# SCH_ea-masterboard_2025-10-05.net
KiCad netlist of a schematic drawn in EasyEDA
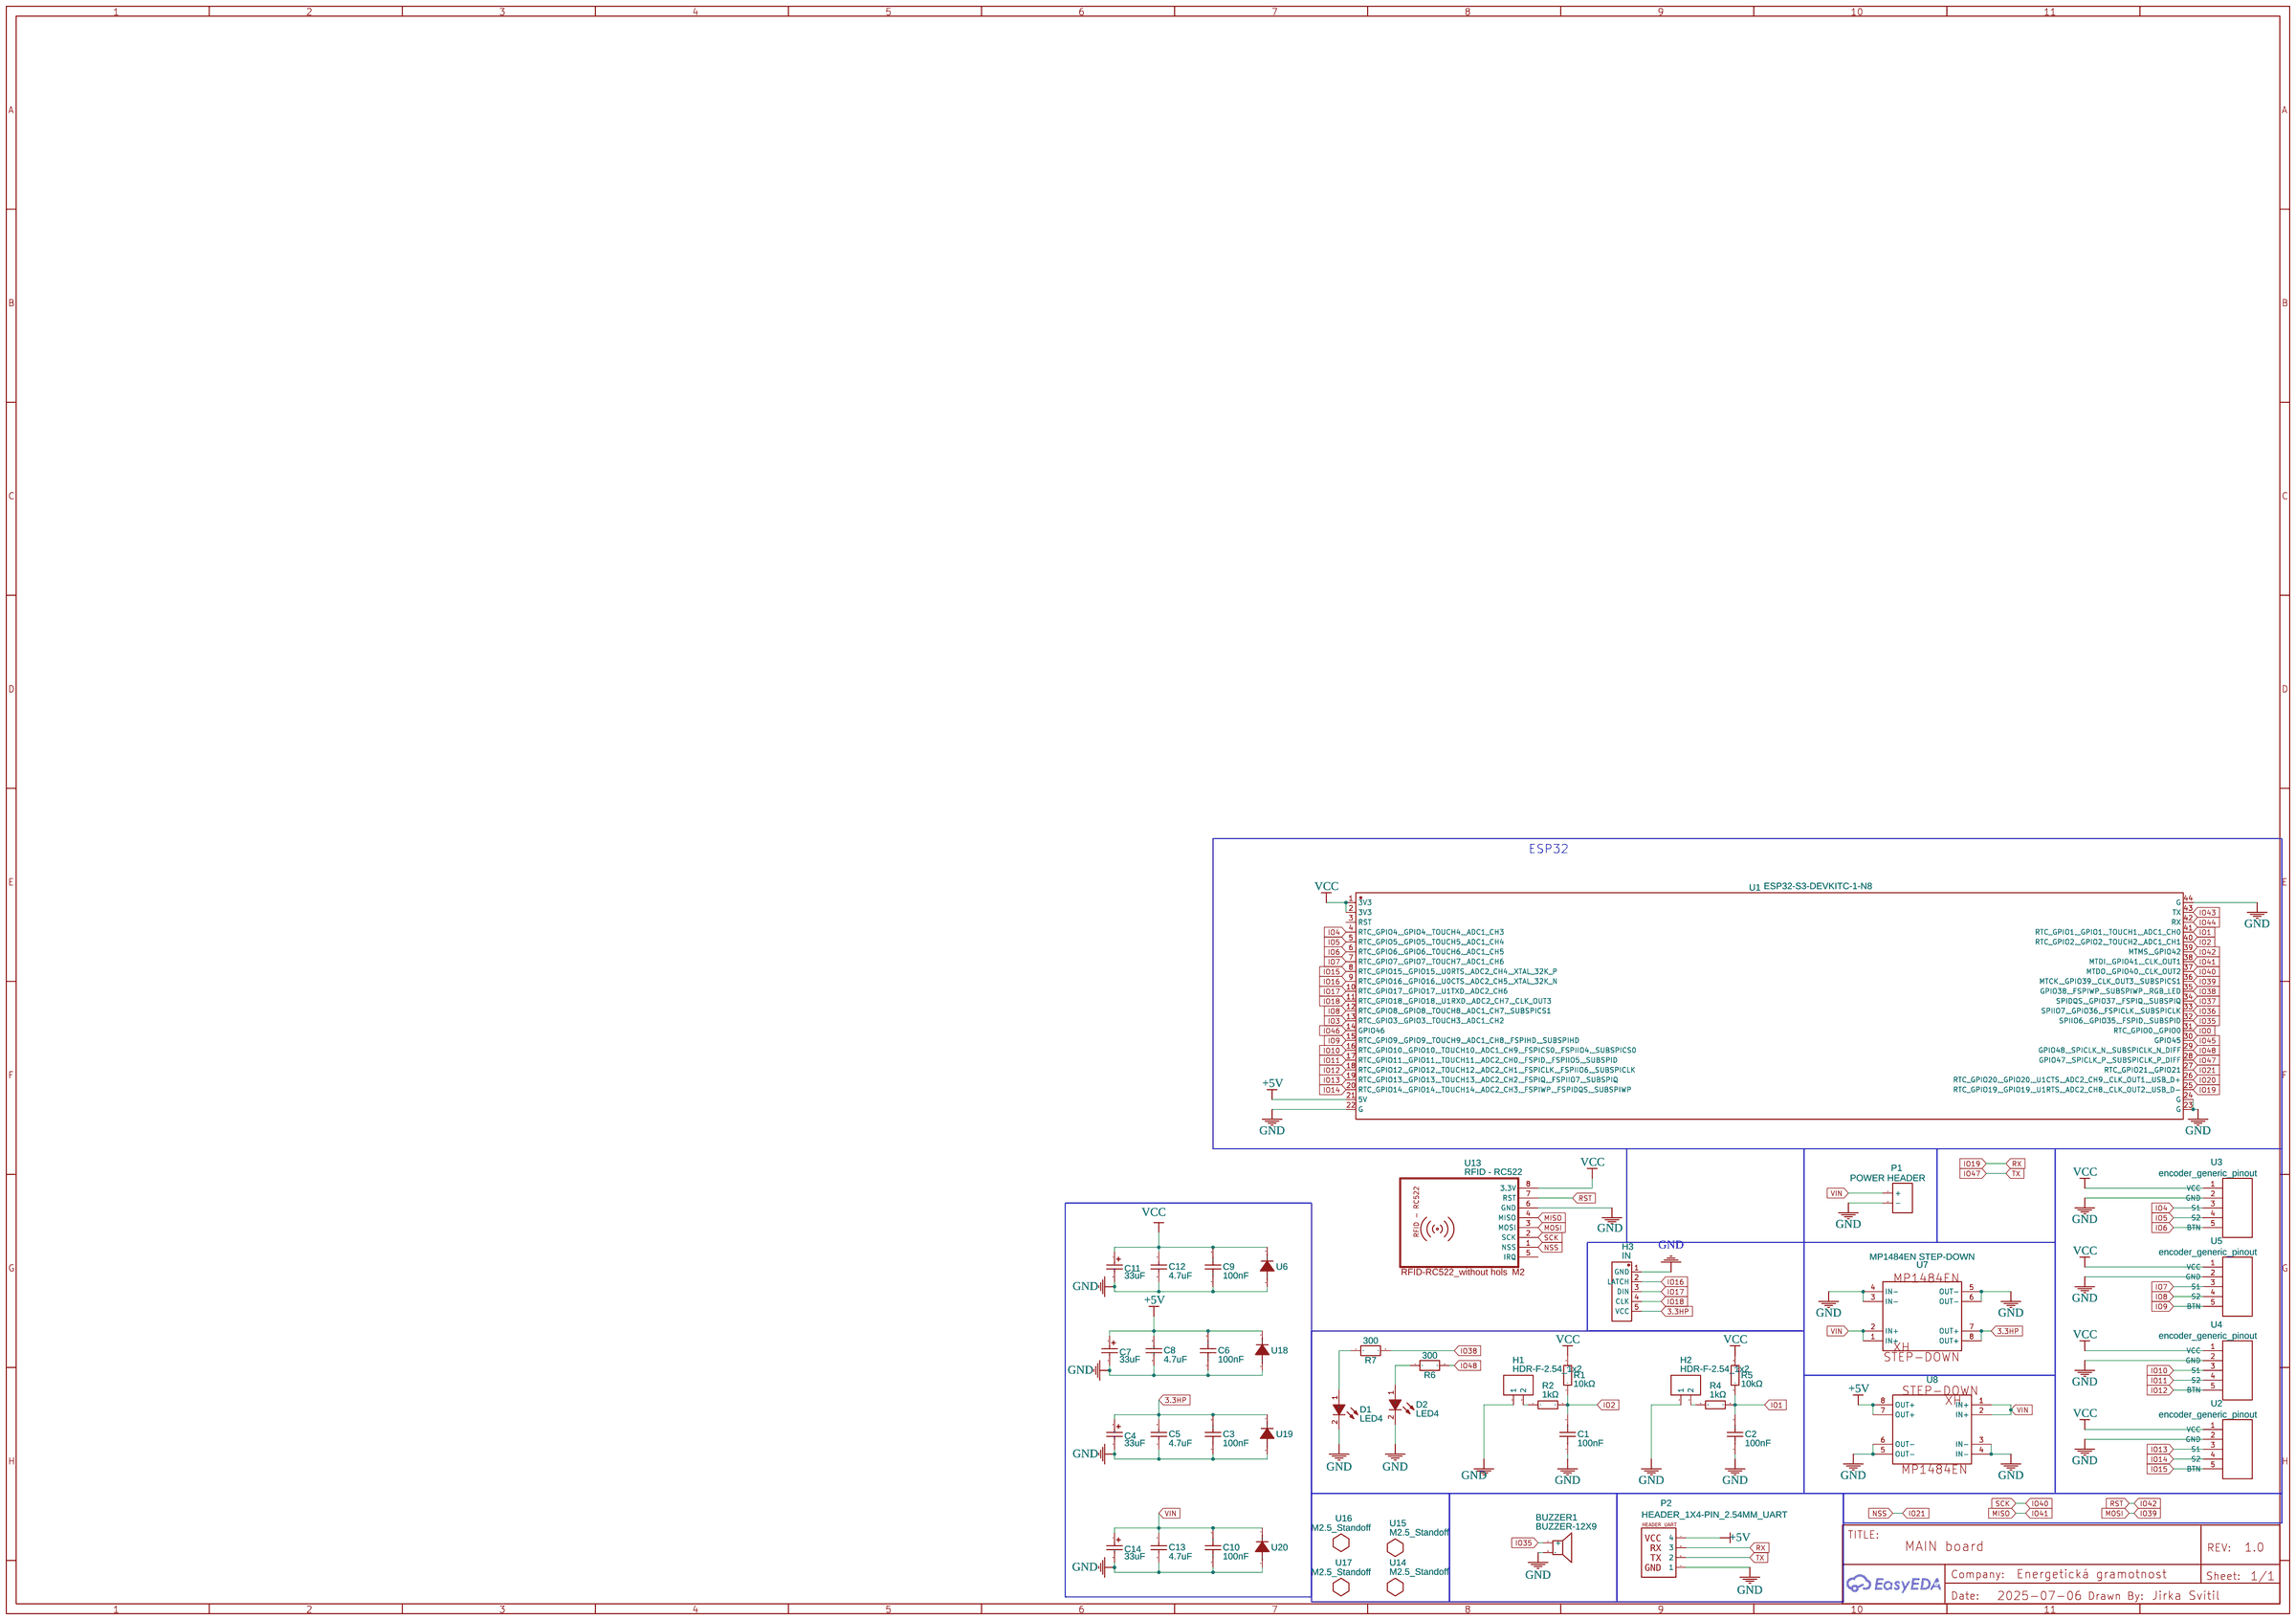
[diagram p0: schematic sheet]

(export (version "E")
  (design (tool "Eeschema 10.0.6"))
  (components
    (comp (ref "BUZZER1")
      (value "BUZZER-12X9")
      (fields (field (name "Manufacturer Part") "buzzer-12X9"))
      (libsource (lib "") (part "BUZZER-12X9"))
    )
    (comp (ref "C1")
      (value "100nF")
      (fields
        (field (name "Manufacturer Part") "CC0603KRX7R9BB104")
        (field (name "Manufacturer") "YAGEO(国巨)")
      )
      (libsource (lib "") (part "CC0603KRX7R9BB104"))
    )
    (comp (ref "C2")
      (value "100nF")
      (fields
        (field (name "Manufacturer Part") "CC0603KRX7R9BB104")
        (field (name "Manufacturer") "YAGEO(国巨)")
      )
      (libsource (lib "") (part "CC0603KRX7R9BB104"))
    )
    (comp (ref "C3")
      (value "100nF")
      (fields
        (field (name "Manufacturer Part") "CC0603KRX7R9BB104")
        (field (name "Manufacturer") "YAGEO(国巨)")
      )
      (libsource (lib "") (part "CC0603KRX7R9BB104"))
    )
    (comp (ref "C4")
      (value "33uF")
      (fields (field (name "Manufacturer Part") "CA45-A010K336T") (field (name "Manufacturer") "湘怡中元/湘江"))
      (libsource (lib "") (part "CA45-A010K336T"))
    )
    (comp (ref "C5")
      (value "4.7uF")
      (fields
        (field (name "Manufacturer Part") "CL10A475KP8NNNC")
        (field (name "Manufacturer") "SAMSUNG(三星)")
      )
      (libsource (lib "") (part "CL10A475KP8NNNC"))
    )
    (comp (ref "C6")
      (value "100nF")
      (fields
        (field (name "Manufacturer Part") "CC0603KRX7R9BB104")
        (field (name "Manufacturer") "YAGEO(国巨)")
      )
      (libsource (lib "") (part "CC0603KRX7R9BB104"))
    )
    (comp (ref "C7")
      (value "33uF")
      (fields (field (name "Manufacturer Part") "CA45-A010K336T") (field (name "Manufacturer") "湘怡中元/湘江"))
      (libsource (lib "") (part "CA45-A010K336T"))
    )
    (comp (ref "C8")
      (value "4.7uF")
      (fields
        (field (name "Manufacturer Part") "CL10A475KP8NNNC")
        (field (name "Manufacturer") "SAMSUNG(三星)")
      )
      (libsource (lib "") (part "CL10A475KP8NNNC"))
    )
    (comp (ref "C9")
      (value "100nF")
      (fields
        (field (name "Manufacturer Part") "CC0603KRX7R9BB104")
        (field (name "Manufacturer") "YAGEO(国巨)")
      )
      (libsource (lib "") (part "CC0603KRX7R9BB104"))
    )
    (comp (ref "C10")
      (value "100nF")
      (fields
        (field (name "Manufacturer Part") "CC0603KRX7R9BB104")
        (field (name "Manufacturer") "YAGEO(国巨)")
      )
      (libsource (lib "") (part "CC0603KRX7R9BB104"))
    )
    (comp (ref "C11")
      (value "33uF")
      (fields (field (name "Manufacturer Part") "CA45-A010K336T") (field (name "Manufacturer") "湘怡中元/湘江"))
      (libsource (lib "") (part "CA45-A010K336T"))
    )
    (comp (ref "C12")
      (value "4.7uF")
      (fields
        (field (name "Manufacturer Part") "CL10A475KP8NNNC")
        (field (name "Manufacturer") "SAMSUNG(三星)")
      )
      (libsource (lib "") (part "CL10A475KP8NNNC"))
    )
    (comp (ref "C13")
      (value "4.7uF")
      (fields
        (field (name "Manufacturer Part") "CL10A475KP8NNNC")
        (field (name "Manufacturer") "SAMSUNG(三星)")
      )
      (libsource (lib "") (part "CL10A475KP8NNNC"))
    )
    (comp (ref "C14")
      (value "33uF")
      (fields (field (name "Manufacturer Part") "CA45-A010K336T") (field (name "Manufacturer") "湘怡中元/湘江"))
      (libsource (lib "") (part "CA45-A010K336T"))
    )
    (comp (ref "D1")
      (value "LED4")
      (fields (field (name "Manufacturer Part") "5600") (field (name "Manufacturer") "VccLite"))
      (libsource (lib "") (part "LED"))
    )
    (comp (ref "D2")
      (value "LED4")
      (fields (field (name "Manufacturer Part") "5600") (field (name "Manufacturer") "VccLite"))
      (libsource (lib "") (part "LED"))
    )
    (comp (ref "H1") (value "HDR-F-2.54_1x2") (libsource (lib "") (part "HDR-F-2.54_1x2")))
    (comp (ref "H2") (value "HDR-F-2.54_1x2") (libsource (lib "") (part "HDR-F-2.54_1x2")))
    (comp (ref "H3") (value "IN") (libsource (lib "") (part "HEADER - 2.54_1X5")))
    (comp (ref "P1")
      (value "POWER HEADER")
      (fields (field (name "Manufacturer Part") "2.54-1*2PFemale") (field (name "Manufacturer") "BOOMELE"))
      (libsource (lib "") (part "POWER HEADER"))
    )
    (comp (ref "P2")
      (value "HEADER_1X4-PIN_2.54MM_UART")
      (fields
        (field (name "Manufacturer Part") "Header-Female-2.54_1x3")
        (field (name "Manufacturer") "Shanzal Firoz")
      )
      (libsource (lib "") (part "HEADER_1X4-PIN_2.54MM_UART"))
    )
    (comp (ref "R1")
      (value "10kΩ")
      (fields (field (name "Manufacturer Part") "SY0603JN10KP") (field (name "Manufacturer") "SANYEAR(叁叶源)"))
      (libsource (lib "") (part "SY0603JN10KP"))
    )
    (comp (ref "R2")
      (value "1kΩ")
      (fields
        (field (name "Manufacturer Part") "0603WAF1001T5E")
        (field (name "Manufacturer") "UNI-ROYAL(厚声)")
      )
      (libsource (lib "") (part "0603WAF1001T5E"))
    )
    (comp (ref "R4")
      (value "1kΩ")
      (fields
        (field (name "Manufacturer Part") "0603WAF1001T5E")
        (field (name "Manufacturer") "UNI-ROYAL(厚声)")
      )
      (libsource (lib "") (part "0603WAF1001T5E"))
    )
    (comp (ref "R5")
      (value "10kΩ")
      (fields (field (name "Manufacturer Part") "SY0603JN10KP") (field (name "Manufacturer") "SANYEAR(叁叶源)"))
      (libsource (lib "") (part "SY0603JN10KP"))
    )
    (comp (ref "R6") (value "300") (libsource (lib "") (part "R_0603_EU")))
    (comp (ref "R7") (value "300") (libsource (lib "") (part "R_0603_EU")))
    (comp (ref "U1")
      (value "ESP32-S3-DEVKITC-1-N8")
      (fields (field (name "Manufacturer") "ESPRESSIF(乐鑫)"))
      (libsource (lib "") (part "ESP32-S3-DEVKITC-1-N8"))
    )
    (comp (ref "U2") (value "encoder_generic_pinout") (libsource (lib "") (part "encoder_generic_pinout")))
    (comp (ref "U3") (value "encoder_generic_pinout") (libsource (lib "") (part "encoder_generic_pinout")))
    (comp (ref "U4") (value "encoder_generic_pinout") (libsource (lib "") (part "encoder_generic_pinout")))
    (comp (ref "U5") (value "encoder_generic_pinout") (libsource (lib "") (part "encoder_generic_pinout")))
    (comp (ref "U6")
      (value "S3M_C4154420")
      (fields (field (name "Manufacturer Part") "S3M") (field (name "Manufacturer") "TWGMC(台湾迪嘉)"))
      (libsource (lib "") (part "S3M_C4154420"))
    )
    (comp (ref "U7") (value "MP1484EN STEP-DOWN") (libsource (lib "") (part "MP1484EN STEP-DOWN_1")))
    (comp (ref "U8") (value "MP1484EN STEP-DOWN") (libsource (lib "") (part "MP1484EN STEP-DOWN")))
    (comp (ref "U13") (value "RFID - RC522") (libsource (lib "") (part "RFID - RC522")))
    (comp (ref "U14") (value "M2.5_Standoff") (libsource (lib "") (part "M2.5_Standoff")))
    (comp (ref "U15") (value "M2.5_Standoff") (libsource (lib "") (part "M2.5_Standoff")))
    (comp (ref "U16") (value "M2.5_Standoff") (libsource (lib "") (part "M2.5_Standoff")))
    (comp (ref "U17") (value "M2.5_Standoff") (libsource (lib "") (part "M2.5_Standoff")))
    (comp (ref "U18")
      (value "S3M_C4154420")
      (fields (field (name "Manufacturer Part") "S3M") (field (name "Manufacturer") "TWGMC(台湾迪嘉)"))
      (libsource (lib "") (part "S3M_C4154420"))
    )
    (comp (ref "U19")
      (value "S3M_C4154420")
      (fields (field (name "Manufacturer Part") "S3M") (field (name "Manufacturer") "TWGMC(台湾迪嘉)"))
      (libsource (lib "") (part "S3M_C4154420"))
    )
    (comp (ref "U20")
      (value "S3M_C4154420")
      (fields (field (name "Manufacturer Part") "S3M") (field (name "Manufacturer") "TWGMC(台湾迪嘉)"))
      (libsource (lib "") (part "S3M_C4154420"))
    )
  )
  (nets
    (net (code "1") (name "+5V") (class "Default")
      (node (ref "C6") (pin "2") (pinfunction "2_2") (pintype "unspecified"))
      (node (ref "C7") (pin "1") (pinfunction "1_1") (pintype "input"))
      (node (ref "C8") (pin "2") (pinfunction "2_2") (pintype "input"))
      (node (ref "P2") (pin "4") (pinfunction "4_4") (pintype "input"))
      (node (ref "U1") (pin "21") (pinfunction "5V_21") (pintype "unspecified"))
      (node (ref "U18") (pin "1") (pinfunction "1_1") (pintype "unspecified"))
      (node (ref "U8") (pin "7") (pinfunction "OUT+_7") (pintype "unspecified"))
      (node (ref "U8") (pin "8") (pinfunction "OUT+_8") (pintype "unspecified"))
    )
    (net (code "2") (name "3.3HP") (class "Default")
      (node (ref "C3") (pin "2") (pinfunction "2_2") (pintype "unspecified"))
      (node (ref "C4") (pin "1") (pinfunction "1_1") (pintype "input"))
      (node (ref "C5") (pin "2") (pinfunction "2_2") (pintype "input"))
      (node (ref "H3") (pin "5") (pinfunction "VCC_5") (pintype "unspecified"))
      (node (ref "U19") (pin "1") (pinfunction "1_1") (pintype "unspecified"))
      (node (ref "U7") (pin "7") (pinfunction "OUT+_7") (pintype "unspecified"))
      (node (ref "U7") (pin "8") (pinfunction "OUT+_8") (pintype "unspecified"))
    )
    (net (code "3") (name "GND") (class "Default")
      (node (ref "BUZZER1") (pin "2") (pinfunction "2_2") (pintype "unspecified"))
      (node (ref "C1") (pin "1") (pinfunction "1_1") (pintype "unspecified"))
      (node (ref "C10") (pin "1") (pinfunction "1_1") (pintype "unspecified"))
      (node (ref "C11") (pin "2") (pinfunction "2_2") (pintype "input"))
      (node (ref "C12") (pin "1") (pinfunction "1_1") (pintype "input"))
      (node (ref "C13") (pin "1") (pinfunction "1_1") (pintype "input"))
      (node (ref "C14") (pin "2") (pinfunction "2_2") (pintype "input"))
      (node (ref "C2") (pin "1") (pinfunction "1_1") (pintype "unspecified"))
      (node (ref "C3") (pin "1") (pinfunction "1_1") (pintype "unspecified"))
      (node (ref "C4") (pin "2") (pinfunction "2_2") (pintype "input"))
      (node (ref "C5") (pin "1") (pinfunction "1_1") (pintype "input"))
      (node (ref "C6") (pin "1") (pinfunction "1_1") (pintype "unspecified"))
      (node (ref "C7") (pin "2") (pinfunction "2_2") (pintype "input"))
      (node (ref "C8") (pin "1") (pinfunction "1_1") (pintype "input"))
      (node (ref "C9") (pin "1") (pinfunction "1_1") (pintype "unspecified"))
      (node (ref "D1") (pin "2") (pinfunction "K_2") (pintype "unspecified"))
      (node (ref "D2") (pin "2") (pinfunction "K_2") (pintype "unspecified"))
      (node (ref "H1") (pin "1") (pinfunction "1_1") (pintype "input"))
      (node (ref "H2") (pin "1") (pinfunction "1_1") (pintype "input"))
      (node (ref "H3") (pin "1") (pinfunction "GND_1") (pintype "unspecified"))
      (node (ref "P1") (pin "2") (pinfunction "-_2") (pintype "input"))
      (node (ref "P2") (pin "1") (pinfunction "1_1") (pintype "input"))
      (node (ref "U1") (pin "22") (pinfunction "G_22") (pintype "unspecified"))
      (node (ref "U1") (pin "23") (pinfunction "G_23") (pintype "unspecified"))
      (node (ref "U1") (pin "24") (pinfunction "G_24") (pintype "unspecified"))
      (node (ref "U1") (pin "44") (pinfunction "G_44") (pintype "unspecified"))
      (node (ref "U13") (pin "6") (pinfunction "GND_6") (pintype "unspecified"))
      (node (ref "U18") (pin "2") (pinfunction "2_2") (pintype "unspecified"))
      (node (ref "U19") (pin "2") (pinfunction "2_2") (pintype "unspecified"))
      (node (ref "U2") (pin "2") (pinfunction "GND_2") (pintype "unspecified"))
      (node (ref "U20") (pin "2") (pinfunction "2_2") (pintype "unspecified"))
      (node (ref "U3") (pin "2") (pinfunction "GND_2") (pintype "unspecified"))
      (node (ref "U4") (pin "2") (pinfunction "GND_2") (pintype "unspecified"))
      (node (ref "U5") (pin "2") (pinfunction "GND_2") (pintype "unspecified"))
      (node (ref "U6") (pin "2") (pinfunction "2_2") (pintype "unspecified"))
      (node (ref "U7") (pin "3") (pinfunction "IN-_3") (pintype "unspecified"))
      (node (ref "U7") (pin "4") (pinfunction "IN-_4") (pintype "unspecified"))
      (node (ref "U7") (pin "5") (pinfunction "OUT-_5") (pintype "unspecified"))
      (node (ref "U7") (pin "6") (pinfunction "OUT-_6") (pintype "unspecified"))
      (node (ref "U8") (pin "3") (pinfunction "IN-_3") (pintype "unspecified"))
      (node (ref "U8") (pin "4") (pinfunction "IN-_4") (pintype "unspecified"))
      (node (ref "U8") (pin "5") (pinfunction "OUT-_5") (pintype "unspecified"))
      (node (ref "U8") (pin "6") (pinfunction "OUT-_6") (pintype "unspecified"))
    )
    (net (code "4") (name "IO0") (class "Default")
      (node (ref "U1") (pin "31") (pinfunction "RTC_GPIO0,_GPIO0_31") (pintype "unspecified"))
    )
    (net (code "5") (name "IO1") (class "Default")
      (node (ref "C2") (pin "2") (pinfunction "2_2") (pintype "unspecified"))
      (node (ref "R4") (pin "2") (pinfunction "2_2") (pintype "input"))
      (node (ref "R5") (pin "1") (pinfunction "1_1") (pintype "unspecified"))
      (node (ref "U1") (pin "41") (pinfunction "RTC_GPIO1,_GPIO1,_TOUCH1,_ADC1_CH0_41") (pintype "unspecified"))
    )
    (net (code "6") (name "IO2") (class "Default")
      (node (ref "C1") (pin "2") (pinfunction "2_2") (pintype "unspecified"))
      (node (ref "R1") (pin "1") (pinfunction "1_1") (pintype "unspecified"))
      (node (ref "R2") (pin "2") (pinfunction "2_2") (pintype "input"))
      (node (ref "U1") (pin "40") (pinfunction "RTC_GPIO2,_GPIO2,_TOUCH2,_ADC1_CH1_40") (pintype "unspecified"))
    )
    (net (code "7") (name "IO3") (class "Default")
      (node (ref "U1") (pin "13") (pinfunction "RTC_GPIO3,_GPIO3,_TOUCH3,_ADC1_CH2_13") (pintype "unspecified"))
    )
    (net (code "8") (name "IO4") (class "Default")
      (node (ref "U1") (pin "4") (pinfunction "RTC_GPIO4,_GPIO4,_TOUCH4,_ADC1_CH3_4") (pintype "unspecified"))
      (node (ref "U3") (pin "3") (pinfunction "S1_3") (pintype "unspecified"))
    )
    (net (code "9") (name "IO5") (class "Default")
      (node (ref "U1") (pin "5") (pinfunction "RTC_GPIO5,_GPIO5,_TOUCH5,_ADC1_CH4_5") (pintype "unspecified"))
      (node (ref "U3") (pin "4") (pinfunction "S2_4") (pintype "unspecified"))
    )
    (net (code "10") (name "IO6") (class "Default")
      (node (ref "U1") (pin "6") (pinfunction "RTC_GPIO6,_GPIO6,_TOUCH6,_ADC1_CH5_6") (pintype "unspecified"))
      (node (ref "U3") (pin "5") (pinfunction "BTN_5") (pintype "unspecified"))
    )
    (net (code "11") (name "IO7") (class "Default")
      (node (ref "U1") (pin "7") (pinfunction "RTC_GPIO7,_GPIO7,_TOUCH7,_ADC1_CH6_7") (pintype "unspecified"))
      (node (ref "U5") (pin "3") (pinfunction "S1_3") (pintype "unspecified"))
    )
    (net (code "12") (name "IO8") (class "Default")
      (node (ref "U1") (pin "12") (pinfunction "RTC_GPIO8,_GPIO8,_TOUCH8,_ADC1_CH7,_SUBSPICS1_12") (pintype "unspecified"))
      (node (ref "U5") (pin "4") (pinfunction "S2_4") (pintype "unspecified"))
    )
    (net (code "13") (name "IO9") (class "Default")
      (node (ref "U1") (pin "15") (pinfunction "RTC_GPIO9,_GPIO9,_TOUCH9,_ADC1_CH8,_FSPIHD,_SUBSPIHD_15") (pintype "unspecified"))
      (node (ref "U5") (pin "5") (pinfunction "BTN_5") (pintype "unspecified"))
    )
    (net (code "14") (name "IO10") (class "Default")
      (node (ref "U1") (pin "16") (pinfunction "RTC_GPIO10,_GPIO10,_TOUCH10,_ADC1_CH9,_FSPICS0,_FSPIIO4,_SUBSPICS0_16") (pintype "unspecified"))
      (node (ref "U4") (pin "3") (pinfunction "S1_3") (pintype "unspecified"))
    )
    (net (code "15") (name "IO11") (class "Default")
      (node (ref "U1") (pin "17") (pinfunction "RTC_GPIO11,_GPIO11,_TOUCH11,_ADC2_CH0,_FSPID,_FSPIIO5,_SUBSPID_17") (pintype "unspecified"))
      (node (ref "U4") (pin "4") (pinfunction "S2_4") (pintype "unspecified"))
    )
    (net (code "16") (name "IO12") (class "Default")
      (node (ref "U1") (pin "18") (pinfunction "RTC_GPIO12,_GPIO12,_TOUCH12,_ADC2_CH1,_FSPICLK,_FSPIIO6,_SUBSPICLK_18") (pintype "unspecified"))
      (node (ref "U4") (pin "5") (pinfunction "BTN_5") (pintype "unspecified"))
    )
    (net (code "17") (name "IO13") (class "Default")
      (node (ref "U1") (pin "19") (pinfunction "RTC_GPIO13,_GPIO13,_TOUCH13,_ADC2_CH2,_FSPIQ,_FSPIIO7,_SUBSPIQ_19") (pintype "unspecified"))
      (node (ref "U2") (pin "3") (pinfunction "S1_3") (pintype "unspecified"))
    )
    (net (code "18") (name "IO14") (class "Default")
      (node (ref "U1") (pin "20") (pinfunction "RTC_GPIO14,_GPIO14,_TOUCH14,_ADC2_CH3,_FSPIWP,_FSPIDQS,_SUBSPIWP_20") (pintype "unspecified"))
      (node (ref "U2") (pin "4") (pinfunction "S2_4") (pintype "unspecified"))
    )
    (net (code "19") (name "IO15") (class "Default")
      (node (ref "U1") (pin "8") (pinfunction "RTC_GPIO15,_GPIO15,_U0RTS,_ADC2_CH4,_XTAL_32K_P_8") (pintype "unspecified"))
      (node (ref "U2") (pin "5") (pinfunction "BTN_5") (pintype "unspecified"))
    )
    (net (code "20") (name "IO16") (class "Default")
      (node (ref "H3") (pin "2") (pinfunction "LATCH_2") (pintype "unspecified"))
      (node (ref "U1") (pin "9") (pinfunction "RTC_GPIO16,_GPIO16,_U0CTS,_ADC2_CH5,_XTAL_32K_N_9") (pintype "unspecified"))
    )
    (net (code "21") (name "IO17") (class "Default")
      (node (ref "H3") (pin "3") (pinfunction "DIN_3") (pintype "unspecified"))
      (node (ref "U1") (pin "10") (pinfunction "RTC_GPIO17,_GPIO17,_U1TXD,_ADC2_CH6_10") (pintype "unspecified"))
    )
    (net (code "22") (name "IO18") (class "Default")
      (node (ref "H3") (pin "4") (pinfunction "CLK_4") (pintype "unspecified"))
      (node (ref "U1") (pin "11") (pinfunction "RTC_GPIO18,_GPIO18,_U1RXD,_ADC2_CH7,_CLK_OUT3_11") (pintype "unspecified"))
    )
    (net (code "23") (name "IO19") (class "Default")
      (node (ref "P2") (pin "3") (pinfunction "3_3") (pintype "input"))
      (node (ref "U1") (pin "25") (pinfunction "RTC_GPIO19,_GPIO19,_U1RTS,_ADC2_CH8,_CLK_OUT2,_USB_D-_25") (pintype "unspecified"))
    )
    (net (code "24") (name "IO20") (class "Default")
      (node (ref "U1") (pin "26") (pinfunction "RTC_GPIO20,_GPIO20,_U1CTS,_ADC2_CH9,_CLK_OUT1,_USB_D+_26") (pintype "unspecified"))
    )
    (net (code "25") (name "IO21") (class "Default")
      (node (ref "U1") (pin "27") (pinfunction "RTC_GPIO21,_GPIO21_27") (pintype "unspecified"))
      (node (ref "U13") (pin "1") (pinfunction "NSS_1") (pintype "unspecified"))
    )
    (net (code "26") (name "IO35") (class "Default")
      (node (ref "BUZZER1") (pin "1") (pinfunction "+_1") (pintype "unspecified"))
      (node (ref "U1") (pin "32") (pinfunction "SPIIO6,_GPIO35,_FSPID,_SUBSPID_32") (pintype "unspecified"))
    )
    (net (code "27") (name "IO36") (class "Default")
      (node (ref "U1") (pin "33") (pinfunction "SPIIO7,_GPIO36,_FSPICLK,_SUBSPICLK_33") (pintype "unspecified"))
    )
    (net (code "28") (name "IO37") (class "Default")
      (node (ref "U1") (pin "34") (pinfunction "SPIDQS,_GPIO37,_FSPIQ,_SUBSPIQ_34") (pintype "unspecified"))
    )
    (net (code "29") (name "IO38") (class "Default")
      (node (ref "R7") (pin "2") (pinfunction "2_2") (pintype "unspecified"))
      (node (ref "U1") (pin "35") (pinfunction "GPIO38,_FSPIWP,_SUBSPIWP,_RGB_LED_35") (pintype "unspecified"))
    )
    (net (code "30") (name "IO39") (class "Default")
      (node (ref "U1") (pin "36") (pinfunction "MTCK,_GPIO39,_CLK_OUT3,_SUBSPICS1_36") (pintype "unspecified"))
      (node (ref "U13") (pin "3") (pinfunction "MOSI_3") (pintype "unspecified"))
    )
    (net (code "31") (name "IO40") (class "Default")
      (node (ref "U1") (pin "37") (pinfunction "MTDO,_GPIO40,_CLK_OUT2_37") (pintype "unspecified"))
      (node (ref "U13") (pin "2") (pinfunction "SCK_2") (pintype "unspecified"))
    )
    (net (code "32") (name "IO41") (class "Default")
      (node (ref "U1") (pin "38") (pinfunction "MTDI,_GPIO41,_CLK_OUT1_38") (pintype "unspecified"))
      (node (ref "U13") (pin "4") (pinfunction "MISO_4") (pintype "unspecified"))
    )
    (net (code "33") (name "IO42") (class "Default")
      (node (ref "U1") (pin "39") (pinfunction "MTMS,_GPIO42_39") (pintype "unspecified"))
      (node (ref "U13") (pin "7") (pinfunction "RST_7") (pintype "unspecified"))
    )
    (net (code "34") (name "IO43") (class "Default")
      (node (ref "U1") (pin "43") (pinfunction "TX_43") (pintype "unspecified"))
    )
    (net (code "35") (name "IO44") (class "Default")
      (node (ref "U1") (pin "42") (pinfunction "RX_42") (pintype "unspecified"))
    )
    (net (code "36") (name "IO45") (class "Default")
      (node (ref "U1") (pin "30") (pinfunction "GPIO45_30") (pintype "unspecified"))
    )
    (net (code "37") (name "IO46") (class "Default")
      (node (ref "U1") (pin "14") (pinfunction "GPIO46_14") (pintype "unspecified"))
    )
    (net (code "38") (name "IO47") (class "Default")
      (node (ref "P2") (pin "2") (pinfunction "2_2") (pintype "input"))
      (node (ref "U1") (pin "28") (pinfunction "GPIO47,_SPICLK_P,_SUBSPICLK_P_DIFF_28") (pintype "unspecified"))
    )
    (net (code "39") (name "IO48") (class "Default")
      (node (ref "R6") (pin "2") (pinfunction "2_2") (pintype "unspecified"))
      (node (ref "U1") (pin "29") (pinfunction "GPIO48,_SPICLK_N,_SUBSPICLK_N_DIFF_29") (pintype "unspecified"))
    )
    (net (code "40") (name "Net-(D1-A)") (class "Default")
      (node (ref "D1") (pin "1") (pinfunction "A_1") (pintype "unspecified"))
      (node (ref "R7") (pin "1") (pinfunction "1_1") (pintype "unspecified"))
    )
    (net (code "41") (name "Net-(D2-A)") (class "Default")
      (node (ref "D2") (pin "1") (pinfunction "A_1") (pintype "unspecified"))
      (node (ref "R6") (pin "1") (pinfunction "1_1") (pintype "unspecified"))
    )
    (net (code "42") (name "Net-(H1-Pad2)") (class "Default")
      (node (ref "H1") (pin "2") (pinfunction "2_2") (pintype "input"))
      (node (ref "R2") (pin "1") (pinfunction "1_1") (pintype "input"))
    )
    (net (code "43") (name "Net-(H2-Pad2)") (class "Default")
      (node (ref "H2") (pin "2") (pinfunction "2_2") (pintype "input"))
      (node (ref "R4") (pin "1") (pinfunction "1_1") (pintype "input"))
    )
    (net (code "44") (name "VCC") (class "Default")
      (node (ref "C11") (pin "1") (pinfunction "1_1") (pintype "input"))
      (node (ref "C12") (pin "2") (pinfunction "2_2") (pintype "input"))
      (node (ref "C9") (pin "2") (pinfunction "2_2") (pintype "unspecified"))
      (node (ref "R1") (pin "2") (pinfunction "2_2") (pintype "unspecified"))
      (node (ref "R5") (pin "2") (pinfunction "2_2") (pintype "unspecified"))
      (node (ref "U1") (pin "1") (pinfunction "3V3_1") (pintype "unspecified"))
      (node (ref "U1") (pin "2") (pinfunction "3V3_2") (pintype "unspecified"))
      (node (ref "U13") (pin "8") (pinfunction "3.3V_8") (pintype "unspecified"))
      (node (ref "U2") (pin "1") (pinfunction "VCC_1") (pintype "unspecified"))
      (node (ref "U3") (pin "1") (pinfunction "VCC_1") (pintype "unspecified"))
      (node (ref "U4") (pin "1") (pinfunction "VCC_1") (pintype "unspecified"))
      (node (ref "U5") (pin "1") (pinfunction "VCC_1") (pintype "unspecified"))
      (node (ref "U6") (pin "1") (pinfunction "1_1") (pintype "unspecified"))
    )
    (net (code "45") (name "VIN") (class "Default")
      (node (ref "C10") (pin "2") (pinfunction "2_2") (pintype "unspecified"))
      (node (ref "C13") (pin "2") (pinfunction "2_2") (pintype "input"))
      (node (ref "C14") (pin "1") (pinfunction "1_1") (pintype "input"))
      (node (ref "P1") (pin "1") (pinfunction "+_1") (pintype "input"))
      (node (ref "U20") (pin "1") (pinfunction "1_1") (pintype "unspecified"))
      (node (ref "U7") (pin "1") (pinfunction "IN+_1") (pintype "unspecified"))
      (node (ref "U7") (pin "2") (pinfunction "IN+_2") (pintype "unspecified"))
      (node (ref "U8") (pin "1") (pinfunction "IN+_1") (pintype "unspecified"))
      (node (ref "U8") (pin "2") (pinfunction "IN+_2") (pintype "unspecified"))
    )
    (net (code "46") (name "unconnected-(U1-RST-Pad3)") (class "Default")
      (node (ref "U1") (pin "3") (pinfunction "RST_3") (pintype "unspecified"))
    )
    (net (code "47") (name "unconnected-(U13-IRQ-Pad5)") (class "Default")
      (node (ref "U13") (pin "5") (pinfunction "IRQ_5") (pintype "unspecified"))
    )
  )
)
